# BigBus.net
KiCad netlist of a schematic drawn in EAGLE
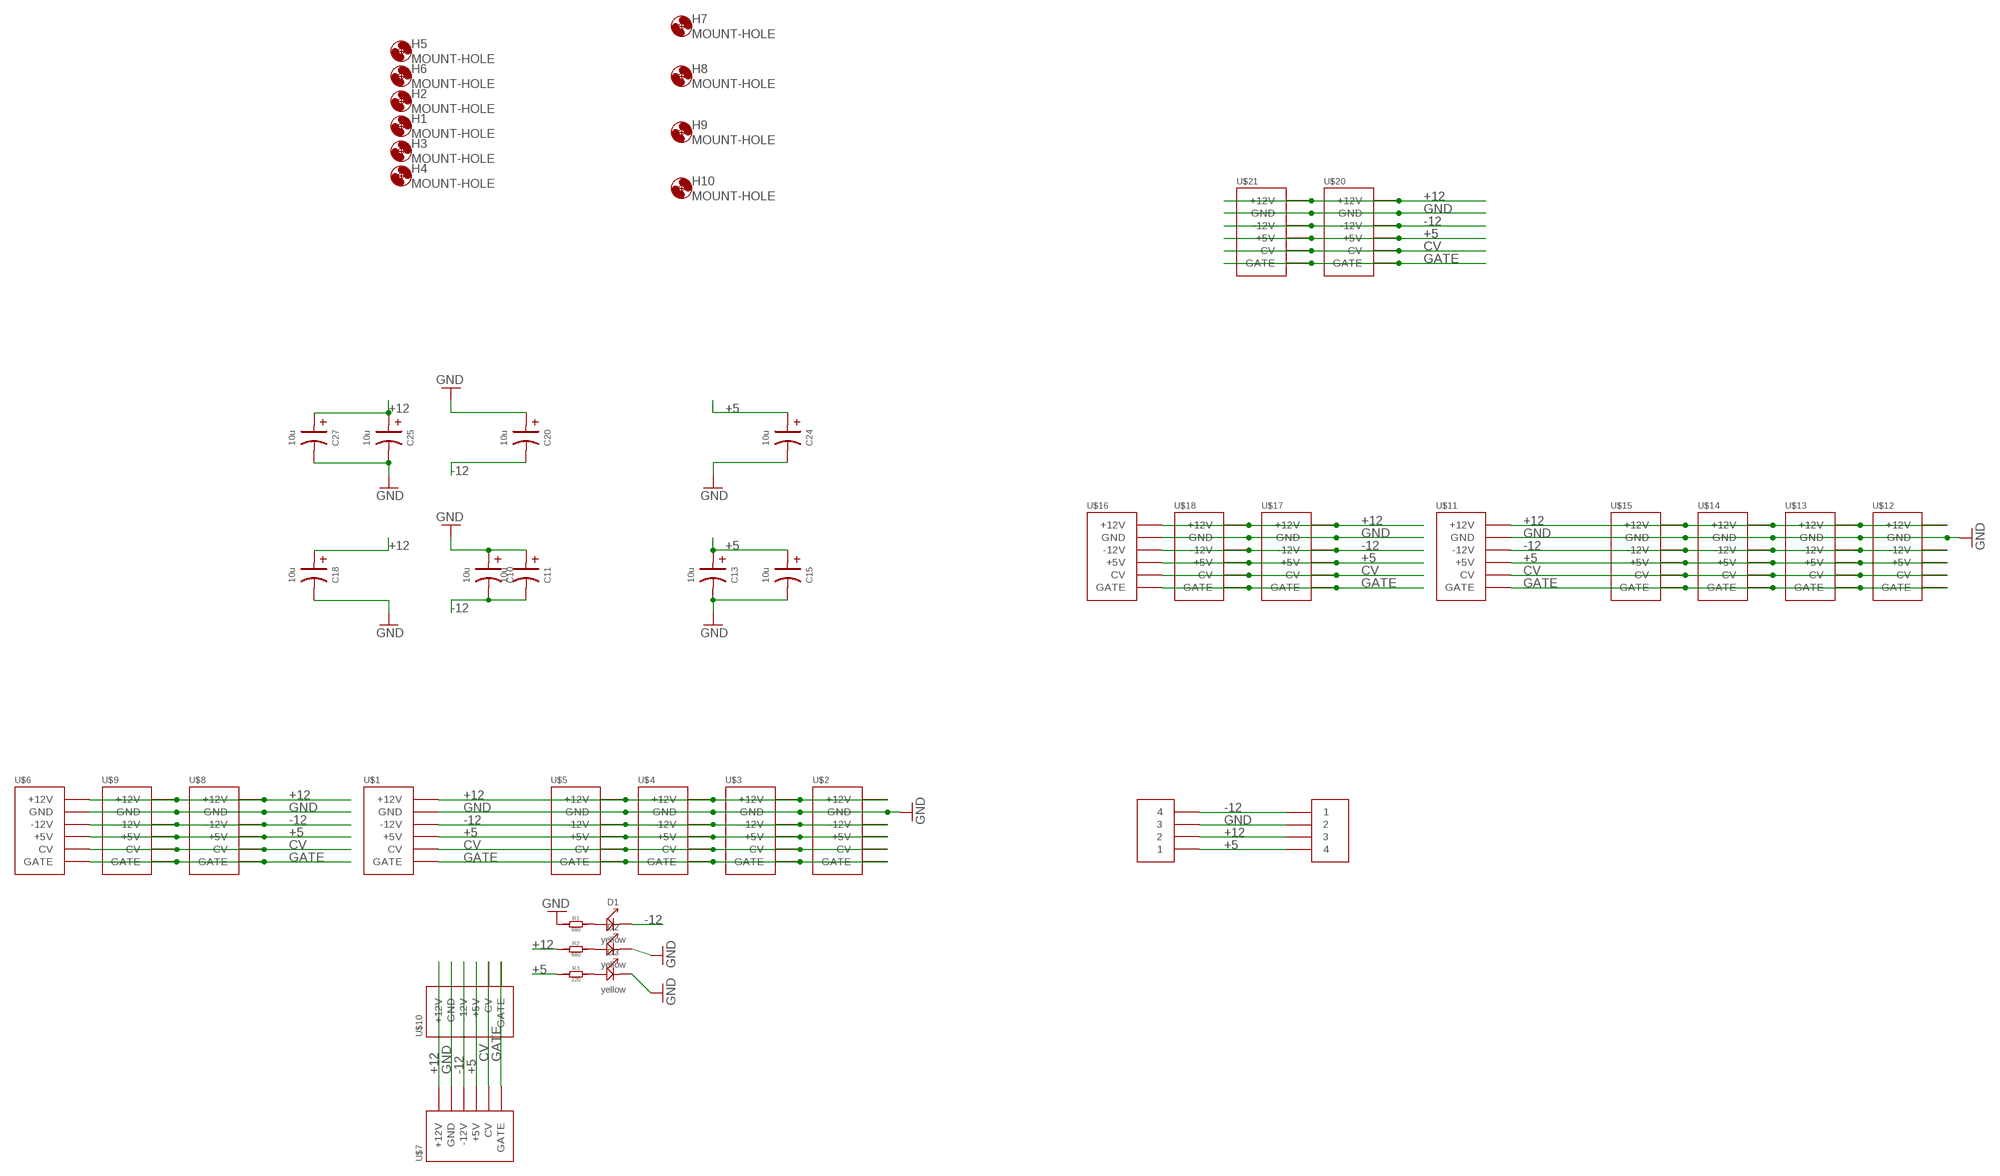
[diagram p0: schematic, sheet 1]

(export (version "E")
  (design (tool "Eeschema 10.0.6"))
  (components
    (comp (ref "C10")
      (value "10u")
      (footprint "eagle-import:AVX-A")
      (libsource (lib "eagle-import") (part "C-POLAR-A"))
    )
    (comp (ref "C11")
      (value "10u")
      (footprint "eagle-import:AVX-A")
      (libsource (lib "eagle-import") (part "C-POLAR-A"))
    )
    (comp (ref "C13")
      (value "10u")
      (footprint "eagle-import:AVX-A")
      (libsource (lib "eagle-import") (part "C-POLAR-A"))
    )
    (comp (ref "C15")
      (value "10u")
      (footprint "eagle-import:AVX-A")
      (libsource (lib "eagle-import") (part "C-POLAR-A"))
    )
    (comp (ref "C18")
      (value "10u")
      (footprint "eagle-import:AVX-A")
      (libsource (lib "eagle-import") (part "C-POLAR-A"))
    )
    (comp (ref "C20")
      (value "10u")
      (footprint "eagle-import:AVX-A")
      (libsource (lib "eagle-import") (part "C-POLAR-A"))
    )
    (comp (ref "C24")
      (value "10u")
      (footprint "eagle-import:AVX-A")
      (libsource (lib "eagle-import") (part "C-POLAR-A"))
    )
    (comp (ref "C25")
      (value "10u")
      (footprint "eagle-import:AVX-A")
      (libsource (lib "eagle-import") (part "C-POLAR-A"))
    )
    (comp (ref "C27")
      (value "10u")
      (footprint "eagle-import:AVX-A")
      (libsource (lib "eagle-import") (part "C-POLAR-A"))
    )
    (comp (ref "D1")
      (value "yellow")
      (footprint "eagle-import:LED0603")
      (libsource (lib "eagle-import") (part "LED"))
    )
    (comp (ref "D2")
      (value "yellow")
      (footprint "eagle-import:LED0603")
      (libsource (lib "eagle-import") (part "LED"))
    )
    (comp (ref "D3")
      (value "yellow")
      (footprint "eagle-import:LED0603")
      (libsource (lib "eagle-import") (part "LED"))
    )
    (comp (ref "H1")
      (value "MOUNT-HOLE")
      (footprint "eagle-import:3.2-NOMARKINGS-SMALLSAFEZONE")
      (libsource (lib "eagle-import") (part "MOUNT-HOLE"))
    )
    (comp (ref "H2")
      (value "MOUNT-HOLE")
      (footprint "eagle-import:3.2-NOMARKINGS-SMALLSAFEZONE")
      (libsource (lib "eagle-import") (part "MOUNT-HOLE"))
    )
    (comp (ref "H3")
      (value "MOUNT-HOLE")
      (footprint "eagle-import:3.2-NOMARKINGS-SMALLSAFEZONE")
      (libsource (lib "eagle-import") (part "MOUNT-HOLE"))
    )
    (comp (ref "H4")
      (value "MOUNT-HOLE")
      (footprint "eagle-import:3.2-NOMARKINGS-SMALLSAFEZONE")
      (libsource (lib "eagle-import") (part "MOUNT-HOLE"))
    )
    (comp (ref "H5")
      (value "MOUNT-HOLE")
      (footprint "eagle-import:3.2-NOMARKINGS-SMALLSAFEZONE")
      (libsource (lib "eagle-import") (part "MOUNT-HOLE"))
    )
    (comp (ref "H6")
      (value "MOUNT-HOLE")
      (footprint "eagle-import:3.2-NOMARKINGS-SMALLSAFEZONE")
      (libsource (lib "eagle-import") (part "MOUNT-HOLE"))
    )
    (comp (ref "H7")
      (value "MOUNT-HOLE")
      (footprint "eagle-import:3.2-NOMARKINGS-SMALLSAFEZONE")
      (libsource (lib "eagle-import") (part "MOUNT-HOLE"))
    )
    (comp (ref "H8")
      (value "MOUNT-HOLE")
      (footprint "eagle-import:3.2-NOMARKINGS-SMALLSAFEZONE")
      (libsource (lib "eagle-import") (part "MOUNT-HOLE"))
    )
    (comp (ref "H9")
      (value "MOUNT-HOLE")
      (footprint "eagle-import:3.2-NOMARKINGS-SMALLSAFEZONE")
      (libsource (lib "eagle-import") (part "MOUNT-HOLE"))
    )
    (comp (ref "H10")
      (value "MOUNT-HOLE")
      (footprint "eagle-import:3.2-NOMARKINGS-SMALLSAFEZONE")
      (libsource (lib "eagle-import") (part "MOUNT-HOLE"))
    )
    (comp (ref "R1")
      (value "680")
      (footprint "eagle-import:R0603")
      (libsource (lib "eagle-import") (part "R-0603"))
    )
    (comp (ref "R2")
      (value "680")
      (footprint "eagle-import:R0603")
      (libsource (lib "eagle-import") (part "R-0603"))
    )
    (comp (ref "R3")
      (value "220")
      (footprint "eagle-import:R0603")
      (libsource (lib "eagle-import") (part "R-0603"))
    )
    (comp (ref "U$1")
      (value "POWERSHROUDED")
      (footprint "eagle-import:POWER_16_SHROUDED")
      (libsource (lib "eagle-import") (part "POWERSHROUDED"))
    )
    (comp (ref "U$2")
      (value "POWER_SHROUDED_NOTEXT")
      (footprint "eagle-import:POWER_16_SHROUDED_NOTEXT")
      (libsource (lib "eagle-import") (part "POWER_SHROUDED_NOTEXT"))
    )
    (comp (ref "U$3")
      (value "POWERSHROUDED")
      (footprint "eagle-import:POWER_16_SHROUDED")
      (libsource (lib "eagle-import") (part "POWERSHROUDED"))
    )
    (comp (ref "U$4")
      (value "POWERSHROUDED")
      (footprint "eagle-import:POWER_16_SHROUDED")
      (libsource (lib "eagle-import") (part "POWERSHROUDED"))
    )
    (comp (ref "U$5")
      (value "POWERSHROUDED")
      (footprint "eagle-import:POWER_16_SHROUDED")
      (libsource (lib "eagle-import") (part "POWERSHROUDED"))
    )
    (comp (ref "U$6")
      (value "POWERSHROUDED")
      (footprint "eagle-import:POWER_16_SHROUDED")
      (libsource (lib "eagle-import") (part "POWERSHROUDED"))
    )
    (comp (ref "U$7")
      (value "POWER_SHROUDED_NOTEXT")
      (footprint "eagle-import:POWER_16_SHROUDED_NOTEXT")
      (libsource (lib "eagle-import") (part "POWER_SHROUDED_NOTEXT"))
    )
    (comp (ref "U$8")
      (value "POWERSHROUDED")
      (footprint "eagle-import:POWER_16_SHROUDED")
      (libsource (lib "eagle-import") (part "POWERSHROUDED"))
    )
    (comp (ref "U$9")
      (value "POWERSHROUDED")
      (footprint "eagle-import:POWER_16_SHROUDED")
      (libsource (lib "eagle-import") (part "POWERSHROUDED"))
    )
    (comp (ref "U$10")
      (value "POWERSHROUDED")
      (footprint "eagle-import:POWER_16_SHROUDED")
      (libsource (lib "eagle-import") (part "POWERSHROUDED"))
    )
    (comp (ref "U$11")
      (value "POWERSHROUDED")
      (footprint "eagle-import:POWER_16_SHROUDED")
      (libsource (lib "eagle-import") (part "POWERSHROUDED"))
    )
    (comp (ref "U$12")
      (value "POWERSHROUDED")
      (footprint "eagle-import:POWER_16_SHROUDED")
      (libsource (lib "eagle-import") (part "POWERSHROUDED"))
    )
    (comp (ref "U$13")
      (value "POWERSHROUDED")
      (footprint "eagle-import:POWER_16_SHROUDED")
      (libsource (lib "eagle-import") (part "POWERSHROUDED"))
    )
    (comp (ref "U$14")
      (value "POWERSHROUDED")
      (footprint "eagle-import:POWER_16_SHROUDED")
      (libsource (lib "eagle-import") (part "POWERSHROUDED"))
    )
    (comp (ref "U$15")
      (value "POWERSHROUDED")
      (footprint "eagle-import:POWER_16_SHROUDED")
      (libsource (lib "eagle-import") (part "POWERSHROUDED"))
    )
    (comp (ref "U$16")
      (value "POWERSHROUDED")
      (footprint "eagle-import:POWER_16_SHROUDED")
      (libsource (lib "eagle-import") (part "POWERSHROUDED"))
    )
    (comp (ref "U$17")
      (value "POWERSHROUDED")
      (footprint "eagle-import:POWER_16_SHROUDED")
      (libsource (lib "eagle-import") (part "POWERSHROUDED"))
    )
    (comp (ref "U$18")
      (value "POWER_SHROUDED_NOTEXT")
      (footprint "eagle-import:POWER_16_SHROUDED_NOTEXT")
      (libsource (lib "eagle-import") (part "POWER_SHROUDED_NOTEXT"))
    )
    (comp (ref "U$19")
      (value "4PIN5MM")
      (footprint "eagle-import:4PIN5MM")
      (libsource (lib "eagle-import") (part "4PIN5MM"))
    )
    (comp (ref "U$20")
      (value "POWERSHROUDED")
      (footprint "eagle-import:POWER_16_SHROUDED")
      (libsource (lib "eagle-import") (part "POWERSHROUDED"))
    )
    (comp (ref "U$21")
      (value "POWER_SHROUDED_NOTEXT")
      (footprint "eagle-import:POWER_16_SHROUDED_NOTEXT")
      (libsource (lib "eagle-import") (part "POWER_SHROUDED_NOTEXT"))
    )
    (comp (ref "U$22")
      (value "4PIN5MM")
      (footprint "eagle-import:4PIN5MM")
      (libsource (lib "eagle-import") (part "4PIN5MM"))
    )
  )
  (nets
    (net (code "1") (name "/+5") (class "Default")
      (node (ref "C13") (pin "+") (pinfunction "1_+") (pintype "bidirectional"))
      (node (ref "C15") (pin "+") (pinfunction "1_+") (pintype "bidirectional"))
      (node (ref "C24") (pin "+") (pinfunction "1_+") (pintype "bidirectional"))
      (node (ref "R3") (pin "1") (pinfunction "1_1") (pintype "bidirectional"))
      (node (ref "U$1") (pin "11") (pinfunction "+5V_11") (pintype "bidirectional"))
      (node (ref "U$1") (pin "12") (pinfunction "+5V_12") (pintype "bidirectional"))
      (node (ref "U$10") (pin "11") (pinfunction "+5V_11") (pintype "bidirectional"))
      (node (ref "U$10") (pin "12") (pinfunction "+5V_12") (pintype "bidirectional"))
      (node (ref "U$11") (pin "11") (pinfunction "+5V_11") (pintype "bidirectional"))
      (node (ref "U$11") (pin "12") (pinfunction "+5V_12") (pintype "bidirectional"))
      (node (ref "U$12") (pin "11") (pinfunction "+5V_11") (pintype "bidirectional"))
      (node (ref "U$12") (pin "12") (pinfunction "+5V_12") (pintype "bidirectional"))
      (node (ref "U$13") (pin "11") (pinfunction "+5V_11") (pintype "bidirectional"))
      (node (ref "U$13") (pin "12") (pinfunction "+5V_12") (pintype "bidirectional"))
      (node (ref "U$14") (pin "11") (pinfunction "+5V_11") (pintype "bidirectional"))
      (node (ref "U$14") (pin "12") (pinfunction "+5V_12") (pintype "bidirectional"))
      (node (ref "U$15") (pin "11") (pinfunction "+5V_11") (pintype "bidirectional"))
      (node (ref "U$15") (pin "12") (pinfunction "+5V_12") (pintype "bidirectional"))
      (node (ref "U$16") (pin "11") (pinfunction "+5V_11") (pintype "bidirectional"))
      (node (ref "U$16") (pin "12") (pinfunction "+5V_12") (pintype "bidirectional"))
      (node (ref "U$17") (pin "11") (pinfunction "+5V_11") (pintype "bidirectional"))
      (node (ref "U$17") (pin "12") (pinfunction "+5V_12") (pintype "bidirectional"))
      (node (ref "U$18") (pin "11") (pinfunction "+5V_11") (pintype "bidirectional"))
      (node (ref "U$18") (pin "12") (pinfunction "+5V_12") (pintype "bidirectional"))
      (node (ref "U$19") (pin "4") (pinfunction "4_4") (pintype "bidirectional"))
      (node (ref "U$2") (pin "11") (pinfunction "+5V_11") (pintype "bidirectional"))
      (node (ref "U$2") (pin "12") (pinfunction "+5V_12") (pintype "bidirectional"))
      (node (ref "U$20") (pin "11") (pinfunction "+5V_11") (pintype "bidirectional"))
      (node (ref "U$20") (pin "12") (pinfunction "+5V_12") (pintype "bidirectional"))
      (node (ref "U$21") (pin "11") (pinfunction "+5V_11") (pintype "bidirectional"))
      (node (ref "U$21") (pin "12") (pinfunction "+5V_12") (pintype "bidirectional"))
      (node (ref "U$22") (pin "1") (pinfunction "1_1") (pintype "bidirectional"))
      (node (ref "U$3") (pin "11") (pinfunction "+5V_11") (pintype "bidirectional"))
      (node (ref "U$3") (pin "12") (pinfunction "+5V_12") (pintype "bidirectional"))
      (node (ref "U$4") (pin "11") (pinfunction "+5V_11") (pintype "bidirectional"))
      (node (ref "U$4") (pin "12") (pinfunction "+5V_12") (pintype "bidirectional"))
      (node (ref "U$5") (pin "11") (pinfunction "+5V_11") (pintype "bidirectional"))
      (node (ref "U$5") (pin "12") (pinfunction "+5V_12") (pintype "bidirectional"))
      (node (ref "U$6") (pin "11") (pinfunction "+5V_11") (pintype "bidirectional"))
      (node (ref "U$6") (pin "12") (pinfunction "+5V_12") (pintype "bidirectional"))
      (node (ref "U$7") (pin "11") (pinfunction "+5V_11") (pintype "bidirectional"))
      (node (ref "U$7") (pin "12") (pinfunction "+5V_12") (pintype "bidirectional"))
      (node (ref "U$8") (pin "11") (pinfunction "+5V_11") (pintype "bidirectional"))
      (node (ref "U$8") (pin "12") (pinfunction "+5V_12") (pintype "bidirectional"))
      (node (ref "U$9") (pin "11") (pinfunction "+5V_11") (pintype "bidirectional"))
      (node (ref "U$9") (pin "12") (pinfunction "+5V_12") (pintype "bidirectional"))
    )
    (net (code "2") (name "/+12") (class "Default")
      (node (ref "C18") (pin "+") (pinfunction "1_+") (pintype "bidirectional"))
      (node (ref "C25") (pin "+") (pinfunction "1_+") (pintype "bidirectional"))
      (node (ref "C27") (pin "+") (pinfunction "1_+") (pintype "bidirectional"))
      (node (ref "R2") (pin "1") (pinfunction "1_1") (pintype "bidirectional"))
      (node (ref "U$1") (pin "10") (pinfunction "+12V_10") (pintype "bidirectional"))
      (node (ref "U$1") (pin "9") (pinfunction "+12V_9") (pintype "bidirectional"))
      (node (ref "U$10") (pin "10") (pinfunction "+12V_10") (pintype "bidirectional"))
      (node (ref "U$10") (pin "9") (pinfunction "+12V_9") (pintype "bidirectional"))
      (node (ref "U$11") (pin "10") (pinfunction "+12V_10") (pintype "bidirectional"))
      (node (ref "U$11") (pin "9") (pinfunction "+12V_9") (pintype "bidirectional"))
      (node (ref "U$12") (pin "10") (pinfunction "+12V_10") (pintype "bidirectional"))
      (node (ref "U$12") (pin "9") (pinfunction "+12V_9") (pintype "bidirectional"))
      (node (ref "U$13") (pin "10") (pinfunction "+12V_10") (pintype "bidirectional"))
      (node (ref "U$13") (pin "9") (pinfunction "+12V_9") (pintype "bidirectional"))
      (node (ref "U$14") (pin "10") (pinfunction "+12V_10") (pintype "bidirectional"))
      (node (ref "U$14") (pin "9") (pinfunction "+12V_9") (pintype "bidirectional"))
      (node (ref "U$15") (pin "10") (pinfunction "+12V_10") (pintype "bidirectional"))
      (node (ref "U$15") (pin "9") (pinfunction "+12V_9") (pintype "bidirectional"))
      (node (ref "U$16") (pin "10") (pinfunction "+12V_10") (pintype "bidirectional"))
      (node (ref "U$16") (pin "9") (pinfunction "+12V_9") (pintype "bidirectional"))
      (node (ref "U$17") (pin "10") (pinfunction "+12V_10") (pintype "bidirectional"))
      (node (ref "U$17") (pin "9") (pinfunction "+12V_9") (pintype "bidirectional"))
      (node (ref "U$18") (pin "10") (pinfunction "+12V_10") (pintype "bidirectional"))
      (node (ref "U$18") (pin "9") (pinfunction "+12V_9") (pintype "bidirectional"))
      (node (ref "U$19") (pin "3") (pinfunction "3_3") (pintype "bidirectional"))
      (node (ref "U$2") (pin "10") (pinfunction "+12V_10") (pintype "bidirectional"))
      (node (ref "U$2") (pin "9") (pinfunction "+12V_9") (pintype "bidirectional"))
      (node (ref "U$20") (pin "10") (pinfunction "+12V_10") (pintype "bidirectional"))
      (node (ref "U$20") (pin "9") (pinfunction "+12V_9") (pintype "bidirectional"))
      (node (ref "U$21") (pin "10") (pinfunction "+12V_10") (pintype "bidirectional"))
      (node (ref "U$21") (pin "9") (pinfunction "+12V_9") (pintype "bidirectional"))
      (node (ref "U$22") (pin "2") (pinfunction "2_2") (pintype "bidirectional"))
      (node (ref "U$3") (pin "10") (pinfunction "+12V_10") (pintype "bidirectional"))
      (node (ref "U$3") (pin "9") (pinfunction "+12V_9") (pintype "bidirectional"))
      (node (ref "U$4") (pin "10") (pinfunction "+12V_10") (pintype "bidirectional"))
      (node (ref "U$4") (pin "9") (pinfunction "+12V_9") (pintype "bidirectional"))
      (node (ref "U$5") (pin "10") (pinfunction "+12V_10") (pintype "bidirectional"))
      (node (ref "U$5") (pin "9") (pinfunction "+12V_9") (pintype "bidirectional"))
      (node (ref "U$6") (pin "10") (pinfunction "+12V_10") (pintype "bidirectional"))
      (node (ref "U$6") (pin "9") (pinfunction "+12V_9") (pintype "bidirectional"))
      (node (ref "U$7") (pin "10") (pinfunction "+12V_10") (pintype "bidirectional"))
      (node (ref "U$7") (pin "9") (pinfunction "+12V_9") (pintype "bidirectional"))
      (node (ref "U$8") (pin "10") (pinfunction "+12V_10") (pintype "bidirectional"))
      (node (ref "U$8") (pin "9") (pinfunction "+12V_9") (pintype "bidirectional"))
      (node (ref "U$9") (pin "10") (pinfunction "+12V_10") (pintype "bidirectional"))
      (node (ref "U$9") (pin "9") (pinfunction "+12V_9") (pintype "bidirectional"))
    )
    (net (code "3") (name "/-12") (class "Default")
      (node (ref "C10") (pin "-") (pinfunction "2_-") (pintype "bidirectional"))
      (node (ref "C11") (pin "-") (pinfunction "2_-") (pintype "bidirectional"))
      (node (ref "C20") (pin "-") (pinfunction "2_-") (pintype "bidirectional"))
      (node (ref "D1") (pin "-") (pinfunction "-_-") (pintype "passive"))
      (node (ref "U$1") (pin "1") (pinfunction "-12V_1") (pintype "bidirectional"))
      (node (ref "U$1") (pin "2") (pinfunction "-12V_2") (pintype "bidirectional"))
      (node (ref "U$10") (pin "1") (pinfunction "-12V_1") (pintype "bidirectional"))
      (node (ref "U$10") (pin "2") (pinfunction "-12V_2") (pintype "bidirectional"))
      (node (ref "U$11") (pin "1") (pinfunction "-12V_1") (pintype "bidirectional"))
      (node (ref "U$11") (pin "2") (pinfunction "-12V_2") (pintype "bidirectional"))
      (node (ref "U$12") (pin "1") (pinfunction "-12V_1") (pintype "bidirectional"))
      (node (ref "U$12") (pin "2") (pinfunction "-12V_2") (pintype "bidirectional"))
      (node (ref "U$13") (pin "1") (pinfunction "-12V_1") (pintype "bidirectional"))
      (node (ref "U$13") (pin "2") (pinfunction "-12V_2") (pintype "bidirectional"))
      (node (ref "U$14") (pin "1") (pinfunction "-12V_1") (pintype "bidirectional"))
      (node (ref "U$14") (pin "2") (pinfunction "-12V_2") (pintype "bidirectional"))
      (node (ref "U$15") (pin "1") (pinfunction "-12V_1") (pintype "bidirectional"))
      (node (ref "U$15") (pin "2") (pinfunction "-12V_2") (pintype "bidirectional"))
      (node (ref "U$16") (pin "1") (pinfunction "-12V_1") (pintype "bidirectional"))
      (node (ref "U$16") (pin "2") (pinfunction "-12V_2") (pintype "bidirectional"))
      (node (ref "U$17") (pin "1") (pinfunction "-12V_1") (pintype "bidirectional"))
      (node (ref "U$17") (pin "2") (pinfunction "-12V_2") (pintype "bidirectional"))
      (node (ref "U$18") (pin "1") (pinfunction "-12V_1") (pintype "bidirectional"))
      (node (ref "U$18") (pin "2") (pinfunction "-12V_2") (pintype "bidirectional"))
      (node (ref "U$19") (pin "1") (pinfunction "1_1") (pintype "bidirectional"))
      (node (ref "U$2") (pin "1") (pinfunction "-12V_1") (pintype "bidirectional"))
      (node (ref "U$2") (pin "2") (pinfunction "-12V_2") (pintype "bidirectional"))
      (node (ref "U$20") (pin "1") (pinfunction "-12V_1") (pintype "bidirectional"))
      (node (ref "U$20") (pin "2") (pinfunction "-12V_2") (pintype "bidirectional"))
      (node (ref "U$21") (pin "1") (pinfunction "-12V_1") (pintype "bidirectional"))
      (node (ref "U$21") (pin "2") (pinfunction "-12V_2") (pintype "bidirectional"))
      (node (ref "U$22") (pin "4") (pinfunction "4_4") (pintype "bidirectional"))
      (node (ref "U$3") (pin "1") (pinfunction "-12V_1") (pintype "bidirectional"))
      (node (ref "U$3") (pin "2") (pinfunction "-12V_2") (pintype "bidirectional"))
      (node (ref "U$4") (pin "1") (pinfunction "-12V_1") (pintype "bidirectional"))
      (node (ref "U$4") (pin "2") (pinfunction "-12V_2") (pintype "bidirectional"))
      (node (ref "U$5") (pin "1") (pinfunction "-12V_1") (pintype "bidirectional"))
      (node (ref "U$5") (pin "2") (pinfunction "-12V_2") (pintype "bidirectional"))
      (node (ref "U$6") (pin "1") (pinfunction "-12V_1") (pintype "bidirectional"))
      (node (ref "U$6") (pin "2") (pinfunction "-12V_2") (pintype "bidirectional"))
      (node (ref "U$7") (pin "1") (pinfunction "-12V_1") (pintype "bidirectional"))
      (node (ref "U$7") (pin "2") (pinfunction "-12V_2") (pintype "bidirectional"))
      (node (ref "U$8") (pin "1") (pinfunction "-12V_1") (pintype "bidirectional"))
      (node (ref "U$8") (pin "2") (pinfunction "-12V_2") (pintype "bidirectional"))
      (node (ref "U$9") (pin "1") (pinfunction "-12V_1") (pintype "bidirectional"))
      (node (ref "U$9") (pin "2") (pinfunction "-12V_2") (pintype "bidirectional"))
    )
    (net (code "4") (name "/CV") (class "Default")
      (node (ref "U$1") (pin "13") (pinfunction "CV_13") (pintype "bidirectional"))
      (node (ref "U$1") (pin "14") (pinfunction "CV_14") (pintype "bidirectional"))
      (node (ref "U$10") (pin "13") (pinfunction "CV_13") (pintype "bidirectional"))
      (node (ref "U$10") (pin "14") (pinfunction "CV_14") (pintype "bidirectional"))
      (node (ref "U$11") (pin "13") (pinfunction "CV_13") (pintype "bidirectional"))
      (node (ref "U$11") (pin "14") (pinfunction "CV_14") (pintype "bidirectional"))
      (node (ref "U$12") (pin "13") (pinfunction "CV_13") (pintype "bidirectional"))
      (node (ref "U$12") (pin "14") (pinfunction "CV_14") (pintype "bidirectional"))
      (node (ref "U$13") (pin "13") (pinfunction "CV_13") (pintype "bidirectional"))
      (node (ref "U$13") (pin "14") (pinfunction "CV_14") (pintype "bidirectional"))
      (node (ref "U$14") (pin "13") (pinfunction "CV_13") (pintype "bidirectional"))
      (node (ref "U$14") (pin "14") (pinfunction "CV_14") (pintype "bidirectional"))
      (node (ref "U$15") (pin "13") (pinfunction "CV_13") (pintype "bidirectional"))
      (node (ref "U$15") (pin "14") (pinfunction "CV_14") (pintype "bidirectional"))
      (node (ref "U$16") (pin "13") (pinfunction "CV_13") (pintype "bidirectional"))
      (node (ref "U$16") (pin "14") (pinfunction "CV_14") (pintype "bidirectional"))
      (node (ref "U$17") (pin "13") (pinfunction "CV_13") (pintype "bidirectional"))
      (node (ref "U$17") (pin "14") (pinfunction "CV_14") (pintype "bidirectional"))
      (node (ref "U$18") (pin "13") (pinfunction "CV_13") (pintype "bidirectional"))
      (node (ref "U$18") (pin "14") (pinfunction "CV_14") (pintype "bidirectional"))
      (node (ref "U$2") (pin "13") (pinfunction "CV_13") (pintype "bidirectional"))
      (node (ref "U$2") (pin "14") (pinfunction "CV_14") (pintype "bidirectional"))
      (node (ref "U$20") (pin "13") (pinfunction "CV_13") (pintype "bidirectional"))
      (node (ref "U$20") (pin "14") (pinfunction "CV_14") (pintype "bidirectional"))
      (node (ref "U$21") (pin "13") (pinfunction "CV_13") (pintype "bidirectional"))
      (node (ref "U$21") (pin "14") (pinfunction "CV_14") (pintype "bidirectional"))
      (node (ref "U$3") (pin "13") (pinfunction "CV_13") (pintype "bidirectional"))
      (node (ref "U$3") (pin "14") (pinfunction "CV_14") (pintype "bidirectional"))
      (node (ref "U$4") (pin "13") (pinfunction "CV_13") (pintype "bidirectional"))
      (node (ref "U$4") (pin "14") (pinfunction "CV_14") (pintype "bidirectional"))
      (node (ref "U$5") (pin "13") (pinfunction "CV_13") (pintype "bidirectional"))
      (node (ref "U$5") (pin "14") (pinfunction "CV_14") (pintype "bidirectional"))
      (node (ref "U$6") (pin "13") (pinfunction "CV_13") (pintype "bidirectional"))
      (node (ref "U$6") (pin "14") (pinfunction "CV_14") (pintype "bidirectional"))
      (node (ref "U$7") (pin "13") (pinfunction "CV_13") (pintype "bidirectional"))
      (node (ref "U$7") (pin "14") (pinfunction "CV_14") (pintype "bidirectional"))
      (node (ref "U$8") (pin "13") (pinfunction "CV_13") (pintype "bidirectional"))
      (node (ref "U$8") (pin "14") (pinfunction "CV_14") (pintype "bidirectional"))
      (node (ref "U$9") (pin "13") (pinfunction "CV_13") (pintype "bidirectional"))
      (node (ref "U$9") (pin "14") (pinfunction "CV_14") (pintype "bidirectional"))
    )
    (net (code "5") (name "/GATE") (class "Default")
      (node (ref "U$1") (pin "15") (pinfunction "GATE_15") (pintype "bidirectional"))
      (node (ref "U$1") (pin "16") (pinfunction "GATE_16") (pintype "bidirectional"))
      (node (ref "U$10") (pin "15") (pinfunction "GATE_15") (pintype "bidirectional"))
      (node (ref "U$10") (pin "16") (pinfunction "GATE_16") (pintype "bidirectional"))
      (node (ref "U$11") (pin "15") (pinfunction "GATE_15") (pintype "bidirectional"))
      (node (ref "U$11") (pin "16") (pinfunction "GATE_16") (pintype "bidirectional"))
      (node (ref "U$12") (pin "15") (pinfunction "GATE_15") (pintype "bidirectional"))
      (node (ref "U$12") (pin "16") (pinfunction "GATE_16") (pintype "bidirectional"))
      (node (ref "U$13") (pin "15") (pinfunction "GATE_15") (pintype "bidirectional"))
      (node (ref "U$13") (pin "16") (pinfunction "GATE_16") (pintype "bidirectional"))
      (node (ref "U$14") (pin "15") (pinfunction "GATE_15") (pintype "bidirectional"))
      (node (ref "U$14") (pin "16") (pinfunction "GATE_16") (pintype "bidirectional"))
      (node (ref "U$15") (pin "15") (pinfunction "GATE_15") (pintype "bidirectional"))
      (node (ref "U$15") (pin "16") (pinfunction "GATE_16") (pintype "bidirectional"))
      (node (ref "U$16") (pin "15") (pinfunction "GATE_15") (pintype "bidirectional"))
      (node (ref "U$16") (pin "16") (pinfunction "GATE_16") (pintype "bidirectional"))
      (node (ref "U$17") (pin "15") (pinfunction "GATE_15") (pintype "bidirectional"))
      (node (ref "U$17") (pin "16") (pinfunction "GATE_16") (pintype "bidirectional"))
      (node (ref "U$18") (pin "15") (pinfunction "GATE_15") (pintype "bidirectional"))
      (node (ref "U$18") (pin "16") (pinfunction "GATE_16") (pintype "bidirectional"))
      (node (ref "U$2") (pin "15") (pinfunction "GATE_15") (pintype "bidirectional"))
      (node (ref "U$2") (pin "16") (pinfunction "GATE_16") (pintype "bidirectional"))
      (node (ref "U$20") (pin "15") (pinfunction "GATE_15") (pintype "bidirectional"))
      (node (ref "U$20") (pin "16") (pinfunction "GATE_16") (pintype "bidirectional"))
      (node (ref "U$21") (pin "15") (pinfunction "GATE_15") (pintype "bidirectional"))
      (node (ref "U$21") (pin "16") (pinfunction "GATE_16") (pintype "bidirectional"))
      (node (ref "U$3") (pin "15") (pinfunction "GATE_15") (pintype "bidirectional"))
      (node (ref "U$3") (pin "16") (pinfunction "GATE_16") (pintype "bidirectional"))
      (node (ref "U$4") (pin "15") (pinfunction "GATE_15") (pintype "bidirectional"))
      (node (ref "U$4") (pin "16") (pinfunction "GATE_16") (pintype "bidirectional"))
      (node (ref "U$5") (pin "15") (pinfunction "GATE_15") (pintype "bidirectional"))
      (node (ref "U$5") (pin "16") (pinfunction "GATE_16") (pintype "bidirectional"))
      (node (ref "U$6") (pin "15") (pinfunction "GATE_15") (pintype "bidirectional"))
      (node (ref "U$6") (pin "16") (pinfunction "GATE_16") (pintype "bidirectional"))
      (node (ref "U$7") (pin "15") (pinfunction "GATE_15") (pintype "bidirectional"))
      (node (ref "U$7") (pin "16") (pinfunction "GATE_16") (pintype "bidirectional"))
      (node (ref "U$8") (pin "15") (pinfunction "GATE_15") (pintype "bidirectional"))
      (node (ref "U$8") (pin "16") (pinfunction "GATE_16") (pintype "bidirectional"))
      (node (ref "U$9") (pin "15") (pinfunction "GATE_15") (pintype "bidirectional"))
      (node (ref "U$9") (pin "16") (pinfunction "GATE_16") (pintype "bidirectional"))
    )
    (net (code "6") (name "GND") (class "Default")
      (node (ref "C10") (pin "+") (pinfunction "1_+") (pintype "bidirectional"))
      (node (ref "C11") (pin "+") (pinfunction "1_+") (pintype "bidirectional"))
      (node (ref "C13") (pin "-") (pinfunction "2_-") (pintype "bidirectional"))
      (node (ref "C15") (pin "-") (pinfunction "2_-") (pintype "bidirectional"))
      (node (ref "C18") (pin "-") (pinfunction "2_-") (pintype "bidirectional"))
      (node (ref "C20") (pin "+") (pinfunction "1_+") (pintype "bidirectional"))
      (node (ref "C24") (pin "-") (pinfunction "2_-") (pintype "bidirectional"))
      (node (ref "C25") (pin "-") (pinfunction "2_-") (pintype "bidirectional"))
      (node (ref "C27") (pin "-") (pinfunction "2_-") (pintype "bidirectional"))
      (node (ref "D2") (pin "-") (pinfunction "-_-") (pintype "passive"))
      (node (ref "D3") (pin "-") (pinfunction "-_-") (pintype "passive"))
      (node (ref "R1") (pin "1") (pinfunction "1_1") (pintype "bidirectional"))
      (node (ref "U$1") (pin "3") (pinfunction "GND_3") (pintype "bidirectional"))
      (node (ref "U$1") (pin "4") (pinfunction "GND_4") (pintype "bidirectional"))
      (node (ref "U$1") (pin "5") (pinfunction "GND_5") (pintype "bidirectional"))
      (node (ref "U$1") (pin "6") (pinfunction "GND_6") (pintype "bidirectional"))
      (node (ref "U$1") (pin "7") (pinfunction "GND_7") (pintype "bidirectional"))
      (node (ref "U$1") (pin "8") (pinfunction "GND_8") (pintype "bidirectional"))
      (node (ref "U$10") (pin "3") (pinfunction "GND_3") (pintype "bidirectional"))
      (node (ref "U$10") (pin "4") (pinfunction "GND_4") (pintype "bidirectional"))
      (node (ref "U$10") (pin "5") (pinfunction "GND_5") (pintype "bidirectional"))
      (node (ref "U$10") (pin "6") (pinfunction "GND_6") (pintype "bidirectional"))
      (node (ref "U$10") (pin "7") (pinfunction "GND_7") (pintype "bidirectional"))
      (node (ref "U$10") (pin "8") (pinfunction "GND_8") (pintype "bidirectional"))
      (node (ref "U$11") (pin "3") (pinfunction "GND_3") (pintype "bidirectional"))
      (node (ref "U$11") (pin "4") (pinfunction "GND_4") (pintype "bidirectional"))
      (node (ref "U$11") (pin "5") (pinfunction "GND_5") (pintype "bidirectional"))
      (node (ref "U$11") (pin "6") (pinfunction "GND_6") (pintype "bidirectional"))
      (node (ref "U$11") (pin "7") (pinfunction "GND_7") (pintype "bidirectional"))
      (node (ref "U$11") (pin "8") (pinfunction "GND_8") (pintype "bidirectional"))
      (node (ref "U$12") (pin "3") (pinfunction "GND_3") (pintype "bidirectional"))
      (node (ref "U$12") (pin "4") (pinfunction "GND_4") (pintype "bidirectional"))
      (node (ref "U$12") (pin "5") (pinfunction "GND_5") (pintype "bidirectional"))
      (node (ref "U$12") (pin "6") (pinfunction "GND_6") (pintype "bidirectional"))
      (node (ref "U$12") (pin "7") (pinfunction "GND_7") (pintype "bidirectional"))
      (node (ref "U$12") (pin "8") (pinfunction "GND_8") (pintype "bidirectional"))
      (node (ref "U$13") (pin "3") (pinfunction "GND_3") (pintype "bidirectional"))
      (node (ref "U$13") (pin "4") (pinfunction "GND_4") (pintype "bidirectional"))
      (node (ref "U$13") (pin "5") (pinfunction "GND_5") (pintype "bidirectional"))
      (node (ref "U$13") (pin "6") (pinfunction "GND_6") (pintype "bidirectional"))
      (node (ref "U$13") (pin "7") (pinfunction "GND_7") (pintype "bidirectional"))
      (node (ref "U$13") (pin "8") (pinfunction "GND_8") (pintype "bidirectional"))
      (node (ref "U$14") (pin "3") (pinfunction "GND_3") (pintype "bidirectional"))
      (node (ref "U$14") (pin "4") (pinfunction "GND_4") (pintype "bidirectional"))
      (node (ref "U$14") (pin "5") (pinfunction "GND_5") (pintype "bidirectional"))
      (node (ref "U$14") (pin "6") (pinfunction "GND_6") (pintype "bidirectional"))
      (node (ref "U$14") (pin "7") (pinfunction "GND_7") (pintype "bidirectional"))
      (node (ref "U$14") (pin "8") (pinfunction "GND_8") (pintype "bidirectional"))
      (node (ref "U$15") (pin "3") (pinfunction "GND_3") (pintype "bidirectional"))
      (node (ref "U$15") (pin "4") (pinfunction "GND_4") (pintype "bidirectional"))
      (node (ref "U$15") (pin "5") (pinfunction "GND_5") (pintype "bidirectional"))
      (node (ref "U$15") (pin "6") (pinfunction "GND_6") (pintype "bidirectional"))
      (node (ref "U$15") (pin "7") (pinfunction "GND_7") (pintype "bidirectional"))
      (node (ref "U$15") (pin "8") (pinfunction "GND_8") (pintype "bidirectional"))
      (node (ref "U$16") (pin "3") (pinfunction "GND_3") (pintype "bidirectional"))
      (node (ref "U$16") (pin "4") (pinfunction "GND_4") (pintype "bidirectional"))
      (node (ref "U$16") (pin "5") (pinfunction "GND_5") (pintype "bidirectional"))
      (node (ref "U$16") (pin "6") (pinfunction "GND_6") (pintype "bidirectional"))
      (node (ref "U$16") (pin "7") (pinfunction "GND_7") (pintype "bidirectional"))
      (node (ref "U$16") (pin "8") (pinfunction "GND_8") (pintype "bidirectional"))
      (node (ref "U$17") (pin "3") (pinfunction "GND_3") (pintype "bidirectional"))
      (node (ref "U$17") (pin "4") (pinfunction "GND_4") (pintype "bidirectional"))
      (node (ref "U$17") (pin "5") (pinfunction "GND_5") (pintype "bidirectional"))
      (node (ref "U$17") (pin "6") (pinfunction "GND_6") (pintype "bidirectional"))
      (node (ref "U$17") (pin "7") (pinfunction "GND_7") (pintype "bidirectional"))
      (node (ref "U$17") (pin "8") (pinfunction "GND_8") (pintype "bidirectional"))
      (node (ref "U$18") (pin "3") (pinfunction "GND_3") (pintype "bidirectional"))
      (node (ref "U$18") (pin "4") (pinfunction "GND_4") (pintype "bidirectional"))
      (node (ref "U$18") (pin "5") (pinfunction "GND_5") (pintype "bidirectional"))
      (node (ref "U$18") (pin "6") (pinfunction "GND_6") (pintype "bidirectional"))
      (node (ref "U$18") (pin "7") (pinfunction "GND_7") (pintype "bidirectional"))
      (node (ref "U$18") (pin "8") (pinfunction "GND_8") (pintype "bidirectional"))
      (node (ref "U$19") (pin "2") (pinfunction "2_2") (pintype "bidirectional"))
      (node (ref "U$2") (pin "3") (pinfunction "GND_3") (pintype "bidirectional"))
      (node (ref "U$2") (pin "4") (pinfunction "GND_4") (pintype "bidirectional"))
      (node (ref "U$2") (pin "5") (pinfunction "GND_5") (pintype "bidirectional"))
      (node (ref "U$2") (pin "6") (pinfunction "GND_6") (pintype "bidirectional"))
      (node (ref "U$2") (pin "7") (pinfunction "GND_7") (pintype "bidirectional"))
      (node (ref "U$2") (pin "8") (pinfunction "GND_8") (pintype "bidirectional"))
      (node (ref "U$20") (pin "3") (pinfunction "GND_3") (pintype "bidirectional"))
      (node (ref "U$20") (pin "4") (pinfunction "GND_4") (pintype "bidirectional"))
      (node (ref "U$20") (pin "5") (pinfunction "GND_5") (pintype "bidirectional"))
      (node (ref "U$20") (pin "6") (pinfunction "GND_6") (pintype "bidirectional"))
      (node (ref "U$20") (pin "7") (pinfunction "GND_7") (pintype "bidirectional"))
      (node (ref "U$20") (pin "8") (pinfunction "GND_8") (pintype "bidirectional"))
      (node (ref "U$21") (pin "3") (pinfunction "GND_3") (pintype "bidirectional"))
      (node (ref "U$21") (pin "4") (pinfunction "GND_4") (pintype "bidirectional"))
      (node (ref "U$21") (pin "5") (pinfunction "GND_5") (pintype "bidirectional"))
      (node (ref "U$21") (pin "6") (pinfunction "GND_6") (pintype "bidirectional"))
      (node (ref "U$21") (pin "7") (pinfunction "GND_7") (pintype "bidirectional"))
      (node (ref "U$21") (pin "8") (pinfunction "GND_8") (pintype "bidirectional"))
      (node (ref "U$22") (pin "3") (pinfunction "3_3") (pintype "bidirectional"))
      (node (ref "U$3") (pin "3") (pinfunction "GND_3") (pintype "bidirectional"))
      (node (ref "U$3") (pin "4") (pinfunction "GND_4") (pintype "bidirectional"))
      (node (ref "U$3") (pin "5") (pinfunction "GND_5") (pintype "bidirectional"))
      (node (ref "U$3") (pin "6") (pinfunction "GND_6") (pintype "bidirectional"))
      (node (ref "U$3") (pin "7") (pinfunction "GND_7") (pintype "bidirectional"))
      (node (ref "U$3") (pin "8") (pinfunction "GND_8") (pintype "bidirectional"))
      (node (ref "U$4") (pin "3") (pinfunction "GND_3") (pintype "bidirectional"))
      (node (ref "U$4") (pin "4") (pinfunction "GND_4") (pintype "bidirectional"))
      (node (ref "U$4") (pin "5") (pinfunction "GND_5") (pintype "bidirectional"))
      (node (ref "U$4") (pin "6") (pinfunction "GND_6") (pintype "bidirectional"))
      (node (ref "U$4") (pin "7") (pinfunction "GND_7") (pintype "bidirectional"))
      (node (ref "U$4") (pin "8") (pinfunction "GND_8") (pintype "bidirectional"))
      (node (ref "U$5") (pin "3") (pinfunction "GND_3") (pintype "bidirectional"))
      (node (ref "U$5") (pin "4") (pinfunction "GND_4") (pintype "bidirectional"))
      (node (ref "U$5") (pin "5") (pinfunction "GND_5") (pintype "bidirectional"))
      (node (ref "U$5") (pin "6") (pinfunction "GND_6") (pintype "bidirectional"))
      (node (ref "U$5") (pin "7") (pinfunction "GND_7") (pintype "bidirectional"))
      (node (ref "U$5") (pin "8") (pinfunction "GND_8") (pintype "bidirectional"))
      (node (ref "U$6") (pin "3") (pinfunction "GND_3") (pintype "bidirectional"))
      (node (ref "U$6") (pin "4") (pinfunction "GND_4") (pintype "bidirectional"))
      (node (ref "U$6") (pin "5") (pinfunction "GND_5") (pintype "bidirectional"))
      (node (ref "U$6") (pin "6") (pinfunction "GND_6") (pintype "bidirectional"))
      (node (ref "U$6") (pin "7") (pinfunction "GND_7") (pintype "bidirectional"))
      (node (ref "U$6") (pin "8") (pinfunction "GND_8") (pintype "bidirectional"))
      (node (ref "U$7") (pin "3") (pinfunction "GND_3") (pintype "bidirectional"))
      (node (ref "U$7") (pin "4") (pinfunction "GND_4") (pintype "bidirectional"))
      (node (ref "U$7") (pin "5") (pinfunction "GND_5") (pintype "bidirectional"))
      (node (ref "U$7") (pin "6") (pinfunction "GND_6") (pintype "bidirectional"))
      (node (ref "U$7") (pin "7") (pinfunction "GND_7") (pintype "bidirectional"))
      (node (ref "U$7") (pin "8") (pinfunction "GND_8") (pintype "bidirectional"))
      (node (ref "U$8") (pin "3") (pinfunction "GND_3") (pintype "bidirectional"))
      (node (ref "U$8") (pin "4") (pinfunction "GND_4") (pintype "bidirectional"))
      (node (ref "U$8") (pin "5") (pinfunction "GND_5") (pintype "bidirectional"))
      (node (ref "U$8") (pin "6") (pinfunction "GND_6") (pintype "bidirectional"))
      (node (ref "U$8") (pin "7") (pinfunction "GND_7") (pintype "bidirectional"))
      (node (ref "U$8") (pin "8") (pinfunction "GND_8") (pintype "bidirectional"))
      (node (ref "U$9") (pin "3") (pinfunction "GND_3") (pintype "bidirectional"))
      (node (ref "U$9") (pin "4") (pinfunction "GND_4") (pintype "bidirectional"))
      (node (ref "U$9") (pin "5") (pinfunction "GND_5") (pintype "bidirectional"))
      (node (ref "U$9") (pin "6") (pinfunction "GND_6") (pintype "bidirectional"))
      (node (ref "U$9") (pin "7") (pinfunction "GND_7") (pintype "bidirectional"))
      (node (ref "U$9") (pin "8") (pinfunction "GND_8") (pintype "bidirectional"))
    )
    (net (code "7") (name "Net-(D1-Pad+)") (class "Default")
      (node (ref "D1") (pin "+") (pinfunction "+_+") (pintype "passive"))
      (node (ref "R1") (pin "2") (pinfunction "2_2") (pintype "bidirectional"))
    )
    (net (code "8") (name "Net-(D2-Pad+)") (class "Default")
      (node (ref "D2") (pin "+") (pinfunction "+_+") (pintype "passive"))
      (node (ref "R2") (pin "2") (pinfunction "2_2") (pintype "bidirectional"))
    )
    (net (code "9") (name "Net-(D3-Pad+)") (class "Default")
      (node (ref "D3") (pin "+") (pinfunction "+_+") (pintype "passive"))
      (node (ref "R3") (pin "2") (pinfunction "2_2") (pintype "bidirectional"))
    )
  )
)
